# circle.net
KiCad netlist of a schematic drawn in EAGLE
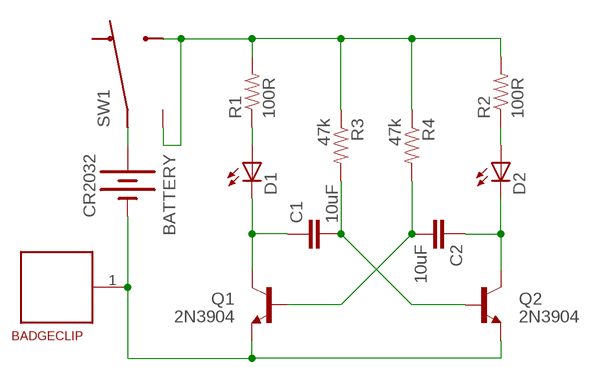
[diagram p0: schematic, sheet 1]

(export (version "E")
  (design (tool "Eeschema 10.0.6"))
  (components
    (comp (ref "BADGECLIP")
      (value "BADGE_CLIP")
      (footprint "eagle-import:BADGE_CLIP")
      (libsource (lib "eagle-import") (part "BADGE_CLIP"))
    )
    (comp (ref "BATTERY")
      (value "CR2032")
      (footprint "eagle-import:BATTCOM_20MM_PTH")
      (libsource (lib "eagle-import") (part "BATTERY20PTH"))
    )
    (comp (ref "C1")
      (value "10uF")
      (footprint "eagle-import:C050-024X044")
      (libsource (lib "eagle-import") (part "C-EU050-024X044"))
    )
    (comp (ref "C2")
      (value "10uF")
      (footprint "eagle-import:C050-024X044")
      (libsource (lib "eagle-import") (part "C-EU050-024X044"))
    )
    (comp (ref "D1")
      (value "LED5MM-KIT")
      (footprint "eagle-import:LED5MM-KIT")
      (libsource (lib "eagle-import") (part "LED5MM-KIT"))
    )
    (comp (ref "D2")
      (value "LED5MM-KIT")
      (footprint "eagle-import:LED5MM-KIT")
      (libsource (lib "eagle-import") (part "LED5MM-KIT"))
    )
    (comp (ref "Q1")
      (value "2N3904")
      (footprint "eagle-import:TO-92-AMMO")
      (libsource (lib "eagle-import") (part "TRANSISTOR_NPNTO-92-AMMO"))
    )
    (comp (ref "Q2")
      (value "2N3904")
      (footprint "eagle-import:TO-92-AMMO")
      (libsource (lib "eagle-import") (part "TRANSISTOR_NPNTO-92-AMMO"))
    )
    (comp (ref "R1")
      (value "100R")
      (footprint "eagle-import:AXIAL-0.4")
      (libsource (lib "eagle-import") (part "RESISTORPTH-1/4W"))
    )
    (comp (ref "R2")
      (value "100R")
      (footprint "eagle-import:AXIAL-0.4")
      (libsource (lib "eagle-import") (part "RESISTORPTH-1/4W"))
    )
    (comp (ref "R3")
      (value "47k")
      (footprint "eagle-import:AXIAL-0.4")
      (libsource (lib "eagle-import") (part "RESISTORPTH-1/4W"))
    )
    (comp (ref "R4")
      (value "47k")
      (footprint "eagle-import:AXIAL-0.4")
      (libsource (lib "eagle-import") (part "RESISTORPTH-1/4W"))
    )
    (comp (ref "SW1")
      (value "0S102011MS2QN1")
      (footprint "eagle-import:0S102011MS2QN1")
      (libsource (lib "eagle-import") (part "0S102011MS2QN1"))
    )
  )
  (nets
    (net (code "1") (name "/1") (class "Default")
      (node (ref "SW1") (pin "1") (pinfunction "1_1") (pintype "power_in"))
    )
    (net (code "2") (name "Net-(BATTERY-+)") (class "Default")
      (node (ref "BATTERY") (pin "1") (pinfunction "+_1") (pintype "power_in"))
      (node (ref "SW1") (pin "2") (pinfunction "2_2") (pintype "power_in"))
    )
    (net (code "3") (name "Net-(BATTERY--)") (class "Default")
      (node (ref "BADGECLIP") (pin "1") (pinfunction "1_1") (pintype "power_in"))
      (node (ref "BATTERY") (pin "2") (pinfunction "-_2") (pintype "power_in"))
      (node (ref "Q1") (pin "1") (pinfunction "E_1") (pintype "passive"))
      (node (ref "Q2") (pin "1") (pinfunction "E_1") (pintype "passive"))
    )
    (net (code "4") (name "Net-(D1-C)") (class "Default")
      (node (ref "C1") (pin "1") (pinfunction "1_1") (pintype "passive"))
      (node (ref "D1") (pin "K") (pinfunction "C_K") (pintype "passive"))
      (node (ref "Q1") (pin "3") (pinfunction "C_3") (pintype "passive"))
    )
    (net (code "5") (name "Net-(D2-C)") (class "Default")
      (node (ref "C2") (pin "1") (pinfunction "1_1") (pintype "passive"))
      (node (ref "D2") (pin "K") (pinfunction "C_K") (pintype "passive"))
      (node (ref "Q2") (pin "3") (pinfunction "C_3") (pintype "passive"))
    )
    (net (code "6") (name "Net-(Q1-B)") (class "Default")
      (node (ref "C2") (pin "2") (pinfunction "2_2") (pintype "passive"))
      (node (ref "Q1") (pin "2") (pinfunction "B_2") (pintype "passive"))
      (node (ref "R4") (pin "P$2") (pinfunction "2_P$2") (pintype "passive"))
    )
    (net (code "7") (name "Net-(Q2-B)") (class "Default")
      (node (ref "C1") (pin "2") (pinfunction "2_2") (pintype "passive"))
      (node (ref "Q2") (pin "2") (pinfunction "B_2") (pintype "passive"))
      (node (ref "R3") (pin "P$2") (pinfunction "2_P$2") (pintype "passive"))
    )
    (net (code "8") (name "Net-(R1-1)") (class "Default")
      (node (ref "D1") (pin "A") (pinfunction "A_A") (pintype "passive"))
      (node (ref "R1") (pin "P$1") (pinfunction "1_P$1") (pintype "passive"))
    )
    (net (code "9") (name "Net-(R1-2)") (class "Default")
      (node (ref "R1") (pin "P$2") (pinfunction "2_P$2") (pintype "passive"))
      (node (ref "R2") (pin "P$2") (pinfunction "2_P$2") (pintype "passive"))
      (node (ref "R3") (pin "P$1") (pinfunction "1_P$1") (pintype "passive"))
      (node (ref "R4") (pin "P$1") (pinfunction "1_P$1") (pintype "passive"))
      (node (ref "SW1") (pin "3") (pinfunction "3_3") (pintype "power_in"))
      (node (ref "SW1") (pin "CASE1") (pinfunction "CASE2_CASE1") (pintype "power_in"))
      (node (ref "SW1") (pin "CASE2") (pinfunction "CASE2_CASE2") (pintype "power_in"))
    )
    (net (code "10") (name "Net-(R2-1)") (class "Default")
      (node (ref "D2") (pin "A") (pinfunction "A_A") (pintype "passive"))
      (node (ref "R2") (pin "P$1") (pinfunction "1_P$1") (pintype "passive"))
    )
  )
)
